# Sensor2.net
KiCad netlist of a schematic drawn in EAGLE
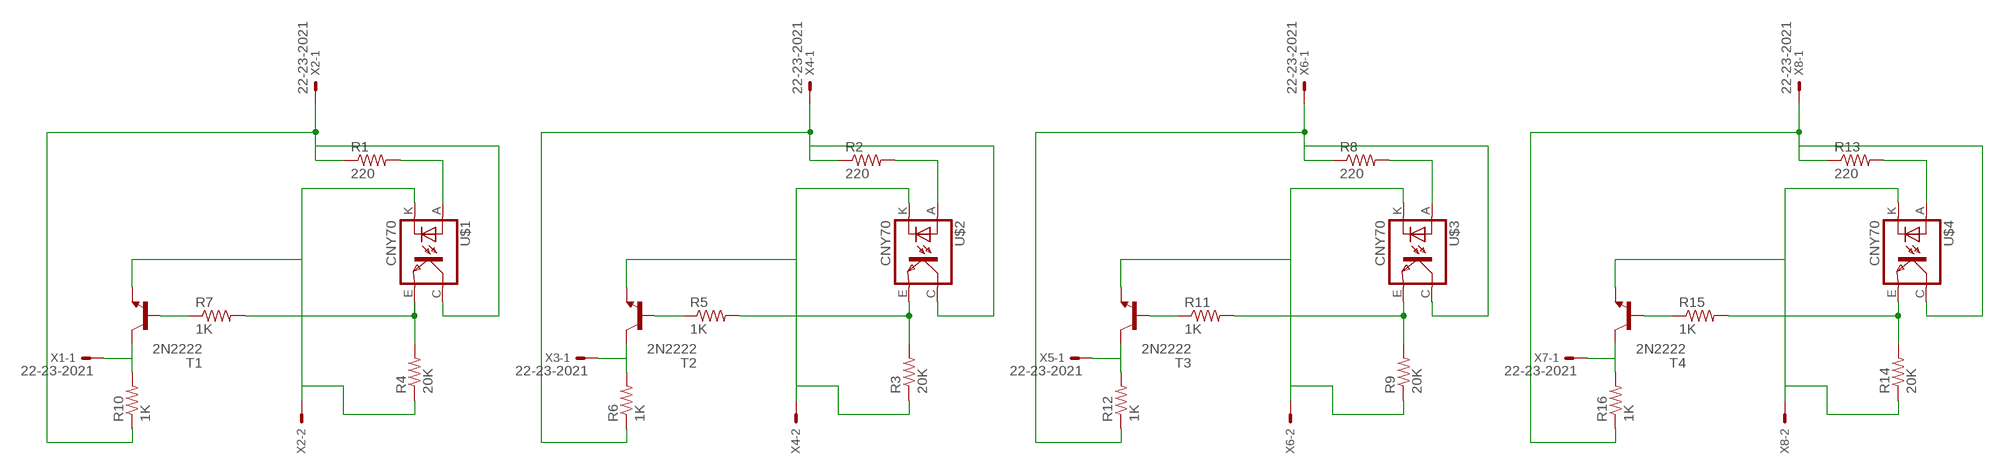
[diagram p0: schematic, sheet 1]

(export (version "E")
  (design (tool "Eeschema 10.0.6"))
  (components
    (comp (ref "R1")
      (value "220")
      (footprint "eagle-import:0204_7")
      (libsource (lib "eagle-import") (part "R-US_0204/7"))
    )
    (comp (ref "R2")
      (value "220")
      (footprint "eagle-import:0204_7")
      (libsource (lib "eagle-import") (part "R-US_0204/7"))
    )
    (comp (ref "R3")
      (value "20K")
      (footprint "eagle-import:0204_7")
      (libsource (lib "eagle-import") (part "R-US_0204/7"))
    )
    (comp (ref "R4")
      (value "20K")
      (footprint "eagle-import:0204_7")
      (libsource (lib "eagle-import") (part "R-US_0204/7"))
    )
    (comp (ref "R5")
      (value "1K")
      (footprint "eagle-import:0204_7")
      (libsource (lib "eagle-import") (part "R-US_0204/7"))
    )
    (comp (ref "R6")
      (value "1K")
      (footprint "eagle-import:0204_7")
      (libsource (lib "eagle-import") (part "R-US_0204/7"))
    )
    (comp (ref "R7")
      (value "1K")
      (footprint "eagle-import:0204_7")
      (libsource (lib "eagle-import") (part "R-US_0204/7"))
    )
    (comp (ref "R8")
      (value "220")
      (footprint "eagle-import:0204_7")
      (libsource (lib "eagle-import") (part "R-US_0204/7"))
    )
    (comp (ref "R9")
      (value "20K")
      (footprint "eagle-import:0204_7")
      (libsource (lib "eagle-import") (part "R-US_0204/7"))
    )
    (comp (ref "R10")
      (value "1K")
      (footprint "eagle-import:0204_7")
      (libsource (lib "eagle-import") (part "R-US_0204/7"))
    )
    (comp (ref "R11")
      (value "1K")
      (footprint "eagle-import:0204_7")
      (libsource (lib "eagle-import") (part "R-US_0204/7"))
    )
    (comp (ref "R12")
      (value "1K")
      (footprint "eagle-import:0204_7")
      (libsource (lib "eagle-import") (part "R-US_0204/7"))
    )
    (comp (ref "R13")
      (value "220")
      (footprint "eagle-import:0204_7")
      (libsource (lib "eagle-import") (part "R-US_0204/7"))
    )
    (comp (ref "R14")
      (value "20K")
      (footprint "eagle-import:0204_7")
      (libsource (lib "eagle-import") (part "R-US_0204/7"))
    )
    (comp (ref "R15")
      (value "1K")
      (footprint "eagle-import:0204_7")
      (libsource (lib "eagle-import") (part "R-US_0204/7"))
    )
    (comp (ref "R16")
      (value "1K")
      (footprint "eagle-import:0204_7")
      (libsource (lib "eagle-import") (part "R-US_0204/7"))
    )
    (comp (ref "T1")
      (value "2N2222")
      (footprint "eagle-import:TO18")
      (libsource (lib "eagle-import") (part "2N2222"))
    )
    (comp (ref "T2")
      (value "2N2222")
      (footprint "eagle-import:TO18")
      (libsource (lib "eagle-import") (part "2N2222"))
    )
    (comp (ref "T3")
      (value "2N2222")
      (footprint "eagle-import:TO18")
      (libsource (lib "eagle-import") (part "2N2222"))
    )
    (comp (ref "T4")
      (value "2N2222")
      (footprint "eagle-import:TO18")
      (libsource (lib "eagle-import") (part "2N2222"))
    )
    (comp (ref "U$1")
      (value "CNY70")
      (footprint "eagle-import:4")
      (libsource (lib "eagle-import") (part "CNY70"))
    )
    (comp (ref "U$2")
      (value "CNY70")
      (footprint "eagle-import:4")
      (libsource (lib "eagle-import") (part "CNY70"))
    )
    (comp (ref "U$3")
      (value "CNY70")
      (footprint "eagle-import:4")
      (libsource (lib "eagle-import") (part "CNY70"))
    )
    (comp (ref "U$4")
      (value "CNY70")
      (footprint "eagle-import:4")
      (libsource (lib "eagle-import") (part "CNY70"))
    )
    (comp (ref "X1")
      (value "22-23-2021")
      (footprint "eagle-import:22-23-2021")
      (fields (field (name "MF") "MOLEX"))
      (libsource (lib "eagle-import") (part "22-23-2021"))
    )
    (comp (ref "X2")
      (value "22-23-2021")
      (footprint "eagle-import:22-23-2021")
      (fields (field (name "MF") "MOLEX"))
      (libsource (lib "eagle-import") (part "22-23-2021"))
    )
    (comp (ref "X3")
      (value "22-23-2021")
      (footprint "eagle-import:22-23-2021")
      (fields (field (name "MF") "MOLEX"))
      (libsource (lib "eagle-import") (part "22-23-2021"))
    )
    (comp (ref "X4")
      (value "22-23-2021")
      (footprint "eagle-import:22-23-2021")
      (fields (field (name "MF") "MOLEX"))
      (libsource (lib "eagle-import") (part "22-23-2021"))
    )
    (comp (ref "X5")
      (value "22-23-2021")
      (footprint "eagle-import:22-23-2021")
      (fields (field (name "MF") "MOLEX"))
      (libsource (lib "eagle-import") (part "22-23-2021"))
    )
    (comp (ref "X6")
      (value "22-23-2021")
      (footprint "eagle-import:22-23-2021")
      (fields (field (name "MF") "MOLEX"))
      (libsource (lib "eagle-import") (part "22-23-2021"))
    )
    (comp (ref "X7")
      (value "22-23-2021")
      (footprint "eagle-import:22-23-2021")
      (fields (field (name "MF") "MOLEX"))
      (libsource (lib "eagle-import") (part "22-23-2021"))
    )
    (comp (ref "X8")
      (value "22-23-2021")
      (footprint "eagle-import:22-23-2021")
      (fields (field (name "MF") "MOLEX"))
      (libsource (lib "eagle-import") (part "22-23-2021"))
    )
  )
  (nets
    (net (code "1") (name "Net-(R1-Pad2)") (class "Default")
      (node (ref "R1") (pin "2") (pinfunction "2_2") (pintype "passive"))
      (node (ref "U$1") (pin "A") (pinfunction "A_A") (pintype "passive"))
    )
    (net (code "2") (name "Net-(R2-Pad2)") (class "Default")
      (node (ref "R2") (pin "2") (pinfunction "2_2") (pintype "passive"))
      (node (ref "U$2") (pin "A") (pinfunction "A_A") (pintype "passive"))
    )
    (net (code "3") (name "Net-(R8-Pad2)") (class "Default")
      (node (ref "R8") (pin "2") (pinfunction "2_2") (pintype "passive"))
      (node (ref "U$3") (pin "A") (pinfunction "A_A") (pintype "passive"))
    )
    (net (code "4") (name "Net-(R13-Pad2)") (class "Default")
      (node (ref "R13") (pin "2") (pinfunction "2_2") (pintype "passive"))
      (node (ref "U$4") (pin "A") (pinfunction "A_A") (pintype "passive"))
    )
    (net (code "5") (name "Net-(T1-B)") (class "Default")
      (node (ref "R7") (pin "1") (pinfunction "1_1") (pintype "passive"))
      (node (ref "T1") (pin "2") (pinfunction "B_2") (pintype "passive"))
    )
    (net (code "6") (name "Net-(T1-C)") (class "Default")
      (node (ref "R10") (pin "2") (pinfunction "2_2") (pintype "passive"))
      (node (ref "T1") (pin "3") (pinfunction "C_3") (pintype "passive"))
      (node (ref "X1") (pin "1") (pinfunction "S_1") (pintype "passive"))
    )
    (net (code "7") (name "Net-(T1-E)") (class "Default")
      (node (ref "R4") (pin "1") (pinfunction "1_1") (pintype "passive"))
      (node (ref "T1") (pin "1") (pinfunction "E_1") (pintype "passive"))
      (node (ref "U$1") (pin "K") (pinfunction "C_K") (pintype "passive"))
      (node (ref "X2") (pin "2") (pinfunction "S_2") (pintype "passive"))
    )
    (net (code "8") (name "Net-(T2-B)") (class "Default")
      (node (ref "R5") (pin "1") (pinfunction "1_1") (pintype "passive"))
      (node (ref "T2") (pin "2") (pinfunction "B_2") (pintype "passive"))
    )
    (net (code "9") (name "Net-(T2-C)") (class "Default")
      (node (ref "R6") (pin "2") (pinfunction "2_2") (pintype "passive"))
      (node (ref "T2") (pin "3") (pinfunction "C_3") (pintype "passive"))
      (node (ref "X3") (pin "1") (pinfunction "S_1") (pintype "passive"))
    )
    (net (code "10") (name "Net-(T2-E)") (class "Default")
      (node (ref "R3") (pin "1") (pinfunction "1_1") (pintype "passive"))
      (node (ref "T2") (pin "1") (pinfunction "E_1") (pintype "passive"))
      (node (ref "U$2") (pin "K") (pinfunction "C_K") (pintype "passive"))
      (node (ref "X4") (pin "2") (pinfunction "S_2") (pintype "passive"))
    )
    (net (code "11") (name "Net-(T3-B)") (class "Default")
      (node (ref "R11") (pin "1") (pinfunction "1_1") (pintype "passive"))
      (node (ref "T3") (pin "2") (pinfunction "B_2") (pintype "passive"))
    )
    (net (code "12") (name "Net-(T3-C)") (class "Default")
      (node (ref "R12") (pin "2") (pinfunction "2_2") (pintype "passive"))
      (node (ref "T3") (pin "3") (pinfunction "C_3") (pintype "passive"))
      (node (ref "X5") (pin "1") (pinfunction "S_1") (pintype "passive"))
    )
    (net (code "13") (name "Net-(T3-E)") (class "Default")
      (node (ref "R9") (pin "1") (pinfunction "1_1") (pintype "passive"))
      (node (ref "T3") (pin "1") (pinfunction "E_1") (pintype "passive"))
      (node (ref "U$3") (pin "K") (pinfunction "C_K") (pintype "passive"))
      (node (ref "X6") (pin "2") (pinfunction "S_2") (pintype "passive"))
    )
    (net (code "14") (name "Net-(T4-B)") (class "Default")
      (node (ref "R15") (pin "1") (pinfunction "1_1") (pintype "passive"))
      (node (ref "T4") (pin "2") (pinfunction "B_2") (pintype "passive"))
    )
    (net (code "15") (name "Net-(T4-C)") (class "Default")
      (node (ref "R16") (pin "2") (pinfunction "2_2") (pintype "passive"))
      (node (ref "T4") (pin "3") (pinfunction "C_3") (pintype "passive"))
      (node (ref "X7") (pin "1") (pinfunction "S_1") (pintype "passive"))
    )
    (net (code "16") (name "Net-(T4-E)") (class "Default")
      (node (ref "R14") (pin "1") (pinfunction "1_1") (pintype "passive"))
      (node (ref "T4") (pin "1") (pinfunction "E_1") (pintype "passive"))
      (node (ref "U$4") (pin "K") (pinfunction "C_K") (pintype "passive"))
      (node (ref "X8") (pin "2") (pinfunction "S_2") (pintype "passive"))
    )
    (net (code "17") (name "Net-(U$1-COL)") (class "Default")
      (node (ref "R1") (pin "1") (pinfunction "1_1") (pintype "passive"))
      (node (ref "R10") (pin "1") (pinfunction "1_1") (pintype "passive"))
      (node (ref "U$1") (pin "C") (pinfunction "COL_C") (pintype "passive"))
      (node (ref "X2") (pin "1") (pinfunction "S_1") (pintype "passive"))
    )
    (net (code "18") (name "Net-(U$1-EMI)") (class "Default")
      (node (ref "R4") (pin "2") (pinfunction "2_2") (pintype "passive"))
      (node (ref "R7") (pin "2") (pinfunction "2_2") (pintype "passive"))
      (node (ref "U$1") (pin "E") (pinfunction "EMI_E") (pintype "passive"))
    )
    (net (code "19") (name "Net-(U$2-COL)") (class "Default")
      (node (ref "R2") (pin "1") (pinfunction "1_1") (pintype "passive"))
      (node (ref "R6") (pin "1") (pinfunction "1_1") (pintype "passive"))
      (node (ref "U$2") (pin "C") (pinfunction "COL_C") (pintype "passive"))
      (node (ref "X4") (pin "1") (pinfunction "S_1") (pintype "passive"))
    )
    (net (code "20") (name "Net-(U$2-EMI)") (class "Default")
      (node (ref "R3") (pin "2") (pinfunction "2_2") (pintype "passive"))
      (node (ref "R5") (pin "2") (pinfunction "2_2") (pintype "passive"))
      (node (ref "U$2") (pin "E") (pinfunction "EMI_E") (pintype "passive"))
    )
    (net (code "21") (name "Net-(U$3-COL)") (class "Default")
      (node (ref "R12") (pin "1") (pinfunction "1_1") (pintype "passive"))
      (node (ref "R8") (pin "1") (pinfunction "1_1") (pintype "passive"))
      (node (ref "U$3") (pin "C") (pinfunction "COL_C") (pintype "passive"))
      (node (ref "X6") (pin "1") (pinfunction "S_1") (pintype "passive"))
    )
    (net (code "22") (name "Net-(U$3-EMI)") (class "Default")
      (node (ref "R11") (pin "2") (pinfunction "2_2") (pintype "passive"))
      (node (ref "R9") (pin "2") (pinfunction "2_2") (pintype "passive"))
      (node (ref "U$3") (pin "E") (pinfunction "EMI_E") (pintype "passive"))
    )
    (net (code "23") (name "Net-(U$4-COL)") (class "Default")
      (node (ref "R13") (pin "1") (pinfunction "1_1") (pintype "passive"))
      (node (ref "R16") (pin "1") (pinfunction "1_1") (pintype "passive"))
      (node (ref "U$4") (pin "C") (pinfunction "COL_C") (pintype "passive"))
      (node (ref "X8") (pin "1") (pinfunction "S_1") (pintype "passive"))
    )
    (net (code "24") (name "Net-(U$4-EMI)") (class "Default")
      (node (ref "R14") (pin "2") (pinfunction "2_2") (pintype "passive"))
      (node (ref "R15") (pin "2") (pinfunction "2_2") (pintype "passive"))
      (node (ref "U$4") (pin "E") (pinfunction "EMI_E") (pintype "passive"))
    )
  )
)
